# Connector_GTX.net
KiCad netlist of a schematic drawn in Altium Designer
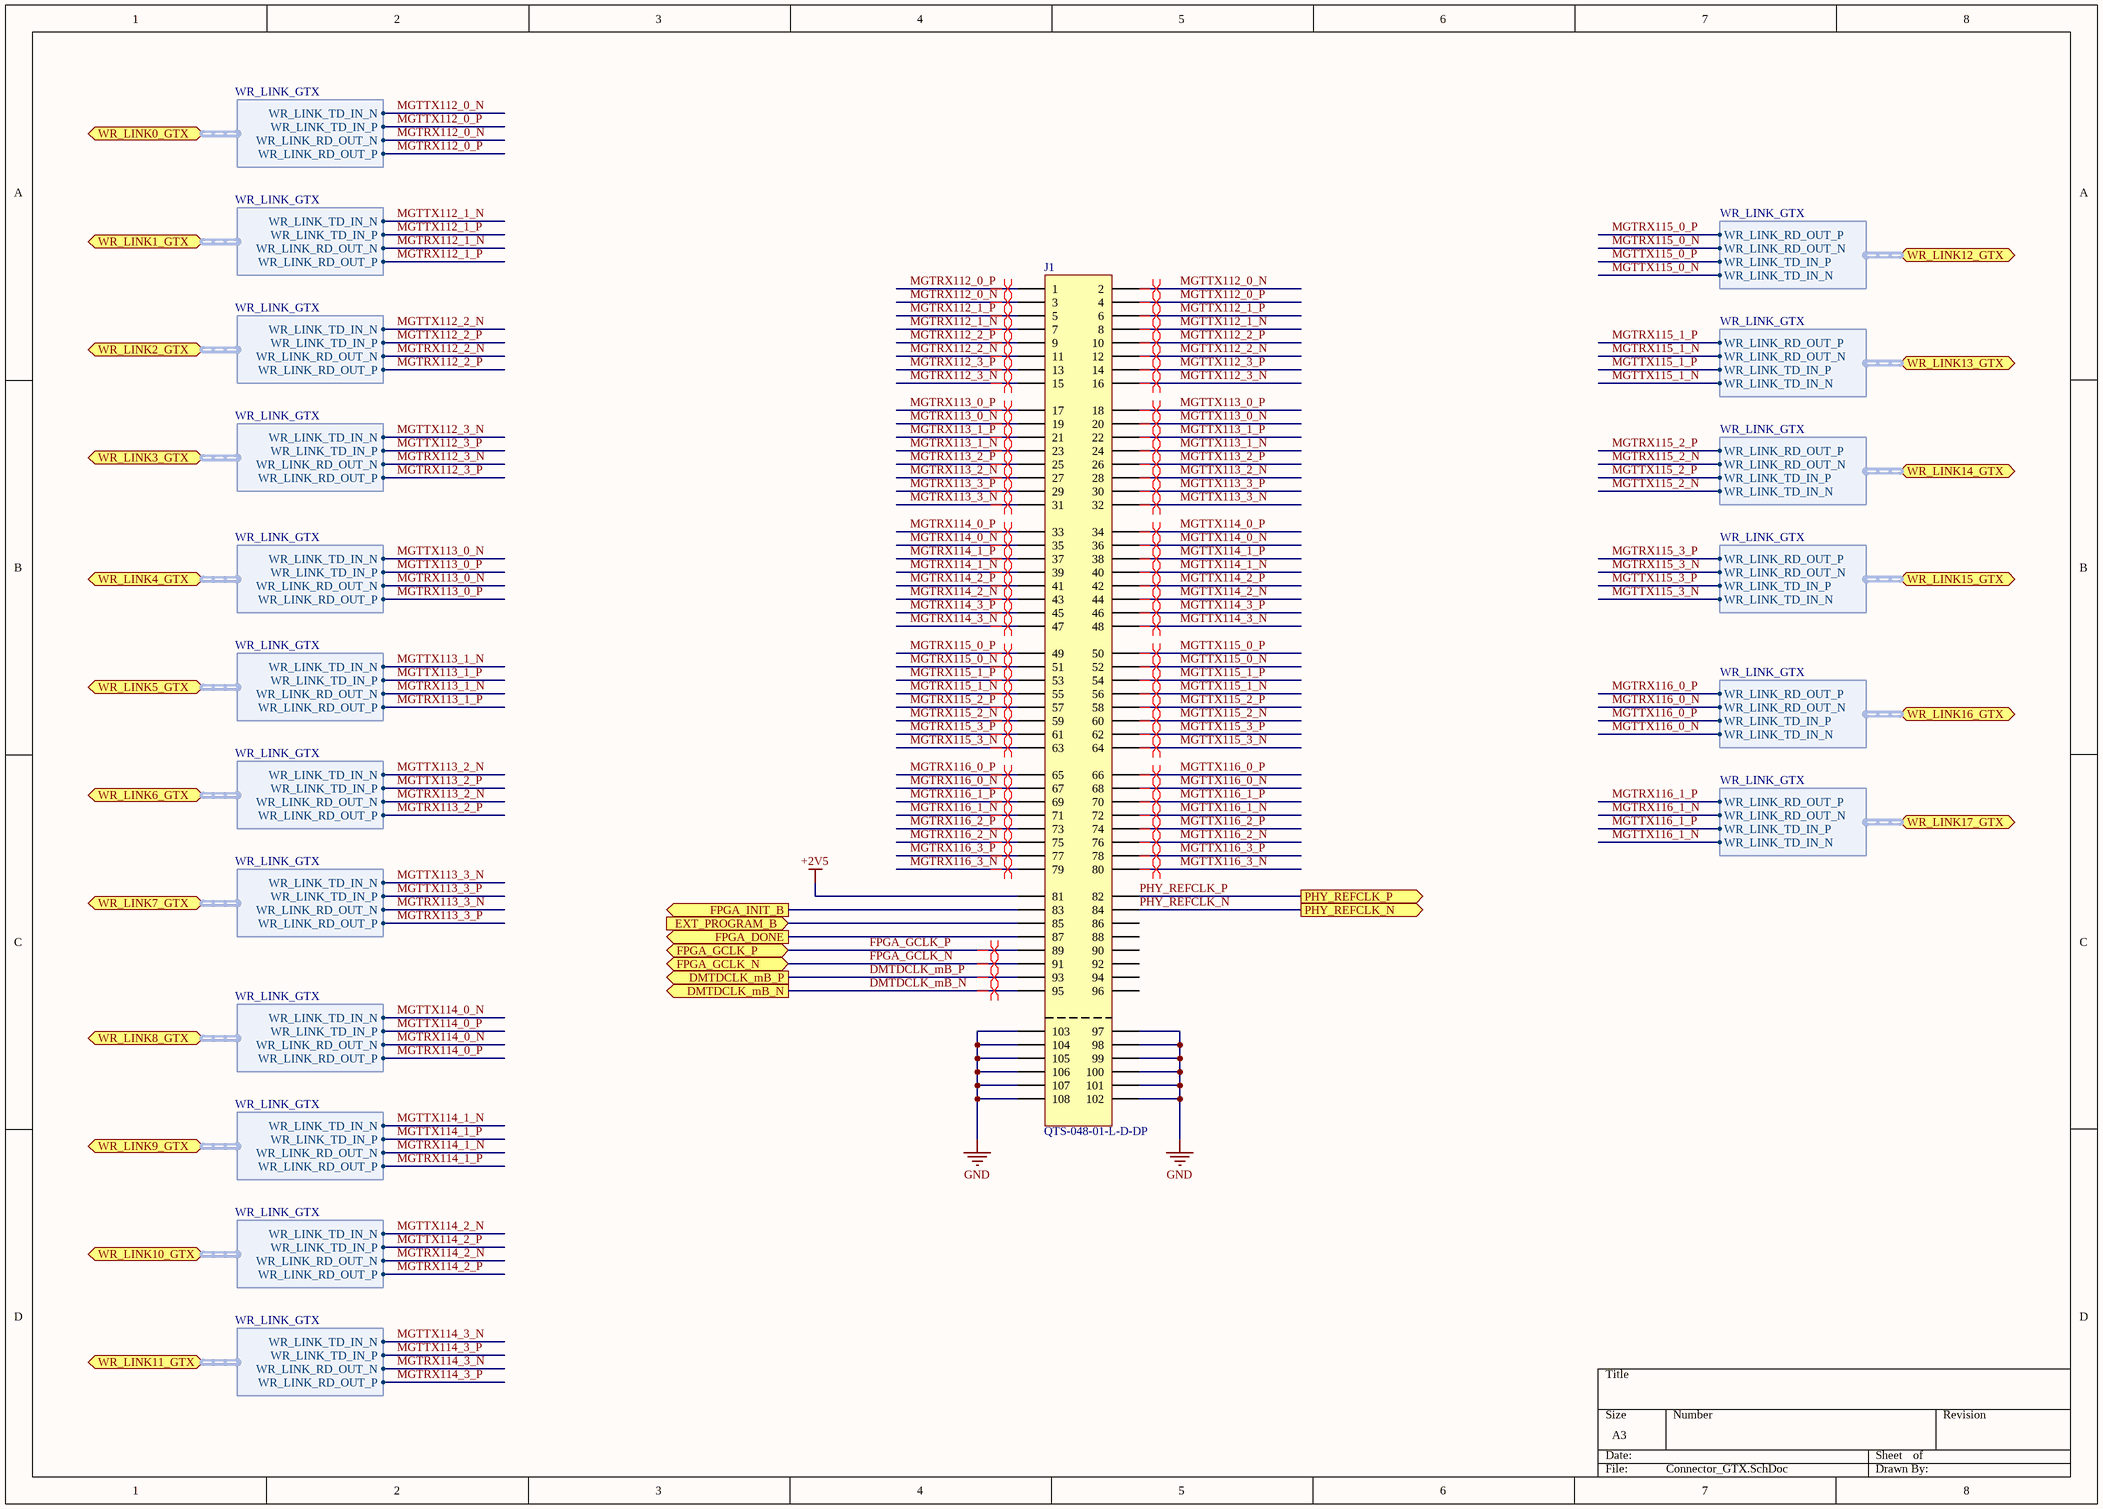
[diagram p0: Connector_GTX.SchDoc]

(export (version "E")
  (design (tool "Eeschema 10.0.6"))
  (components
    (comp (ref "J1")
      (value "QTS-048-01-L-D-DP")
      (footprint "QTS-048-XX-X-D-DP-A")
      (description "High Speed Ground Plane Header")
      (libsource (lib "wr_switch") (part "QTS-048-01-L-D-DP"))
    )
  )
  (nets
    (net (code "2") (name "+2V5") (class "Default")
      (node (ref "J1") (pin "81") (pinfunction "81_81") (pintype "passive"))
    )
    (net (code "3") (name "/DMTDCLK_mB_N") (class "Default")
      (node (ref "J1") (pin "95") (pinfunction "95_95") (pintype "passive"))
    )
    (net (code "4") (name "/DMTDCLK_mB_P") (class "Default")
      (node (ref "J1") (pin "93") (pinfunction "93_93") (pintype "passive"))
    )
    (net (code "5") (name "/EXT_PROGRAM_B") (class "Default")
      (node (ref "J1") (pin "85") (pinfunction "85_85") (pintype "passive"))
    )
    (net (code "6") (name "/FPGA_DONE") (class "Default")
      (node (ref "J1") (pin "87") (pinfunction "87_87") (pintype "passive"))
    )
    (net (code "7") (name "/FPGA_GCLK_N") (class "Default")
      (node (ref "J1") (pin "91") (pinfunction "91_91") (pintype "passive"))
    )
    (net (code "8") (name "/FPGA_GCLK_P") (class "Default")
      (node (ref "J1") (pin "89") (pinfunction "89_89") (pintype "passive"))
    )
    (net (code "9") (name "/FPGA_INIT_B") (class "Default")
      (node (ref "J1") (pin "83") (pinfunction "83_83") (pintype "passive"))
    )
    (net (code "10") (name "/MGTRX112_0_N") (class "Default")
      (node (ref "J1") (pin "3") (pinfunction "3_3") (pintype "passive"))
    )
    (net (code "11") (name "/MGTRX112_0_P") (class "Default")
      (node (ref "J1") (pin "1") (pinfunction "1_1") (pintype "passive"))
    )
    (net (code "12") (name "/MGTRX112_1_N") (class "Default")
      (node (ref "J1") (pin "7") (pinfunction "7_7") (pintype "passive"))
    )
    (net (code "13") (name "/MGTRX112_1_P") (class "Default")
      (node (ref "J1") (pin "5") (pinfunction "5_5") (pintype "passive"))
    )
    (net (code "14") (name "/MGTRX112_2_N") (class "Default")
      (node (ref "J1") (pin "11") (pinfunction "11_11") (pintype "passive"))
    )
    (net (code "15") (name "/MGTRX112_2_P") (class "Default")
      (node (ref "J1") (pin "9") (pinfunction "9_9") (pintype "passive"))
    )
    (net (code "16") (name "/MGTRX112_3_N") (class "Default")
      (node (ref "J1") (pin "15") (pinfunction "15_15") (pintype "passive"))
    )
    (net (code "17") (name "/MGTRX112_3_P") (class "Default")
      (node (ref "J1") (pin "13") (pinfunction "13_13") (pintype "passive"))
    )
    (net (code "18") (name "/MGTRX113_0_N") (class "Default")
      (node (ref "J1") (pin "19") (pinfunction "19_19") (pintype "passive"))
    )
    (net (code "19") (name "/MGTRX113_0_P") (class "Default")
      (node (ref "J1") (pin "17") (pinfunction "17_17") (pintype "passive"))
    )
    (net (code "20") (name "/MGTRX113_1_N") (class "Default")
      (node (ref "J1") (pin "23") (pinfunction "23_23") (pintype "passive"))
    )
    (net (code "21") (name "/MGTRX113_1_P") (class "Default")
      (node (ref "J1") (pin "21") (pinfunction "21_21") (pintype "passive"))
    )
    (net (code "22") (name "/MGTRX113_2_N") (class "Default")
      (node (ref "J1") (pin "27") (pinfunction "27_27") (pintype "passive"))
    )
    (net (code "23") (name "/MGTRX113_2_P") (class "Default")
      (node (ref "J1") (pin "25") (pinfunction "25_25") (pintype "passive"))
    )
    (net (code "24") (name "/MGTRX113_3_N") (class "Default")
      (node (ref "J1") (pin "31") (pinfunction "31_31") (pintype "passive"))
    )
    (net (code "25") (name "/MGTRX113_3_P") (class "Default")
      (node (ref "J1") (pin "29") (pinfunction "29_29") (pintype "passive"))
    )
    (net (code "26") (name "/MGTRX114_0_N") (class "Default")
      (node (ref "J1") (pin "35") (pinfunction "35_35") (pintype "passive"))
    )
    (net (code "27") (name "/MGTRX114_0_P") (class "Default")
      (node (ref "J1") (pin "33") (pinfunction "33_33") (pintype "passive"))
    )
    (net (code "28") (name "/MGTRX114_1_N") (class "Default")
      (node (ref "J1") (pin "39") (pinfunction "39_39") (pintype "passive"))
    )
    (net (code "29") (name "/MGTRX114_1_P") (class "Default")
      (node (ref "J1") (pin "37") (pinfunction "37_37") (pintype "passive"))
    )
    (net (code "30") (name "/MGTRX114_2_N") (class "Default")
      (node (ref "J1") (pin "43") (pinfunction "43_43") (pintype "passive"))
    )
    (net (code "31") (name "/MGTRX114_2_P") (class "Default")
      (node (ref "J1") (pin "41") (pinfunction "41_41") (pintype "passive"))
    )
    (net (code "32") (name "/MGTRX114_3_N") (class "Default")
      (node (ref "J1") (pin "47") (pinfunction "47_47") (pintype "passive"))
    )
    (net (code "33") (name "/MGTRX114_3_P") (class "Default")
      (node (ref "J1") (pin "45") (pinfunction "45_45") (pintype "passive"))
    )
    (net (code "34") (name "/MGTRX115_0_N") (class "Default")
      (node (ref "J1") (pin "51") (pinfunction "51_51") (pintype "passive"))
    )
    (net (code "35") (name "/MGTRX115_0_P") (class "Default")
      (node (ref "J1") (pin "49") (pinfunction "49_49") (pintype "passive"))
    )
    (net (code "36") (name "/MGTRX115_1_N") (class "Default")
      (node (ref "J1") (pin "55") (pinfunction "55_55") (pintype "passive"))
    )
    (net (code "37") (name "/MGTRX115_1_P") (class "Default")
      (node (ref "J1") (pin "53") (pinfunction "53_53") (pintype "passive"))
    )
    (net (code "38") (name "/MGTRX115_2_N") (class "Default")
      (node (ref "J1") (pin "59") (pinfunction "59_59") (pintype "passive"))
    )
    (net (code "39") (name "/MGTRX115_2_P") (class "Default")
      (node (ref "J1") (pin "57") (pinfunction "57_57") (pintype "passive"))
    )
    (net (code "40") (name "/MGTRX115_3_N") (class "Default")
      (node (ref "J1") (pin "63") (pinfunction "63_63") (pintype "passive"))
    )
    (net (code "41") (name "/MGTRX115_3_P") (class "Default")
      (node (ref "J1") (pin "61") (pinfunction "61_61") (pintype "passive"))
    )
    (net (code "42") (name "/MGTRX116_0_N") (class "Default")
      (node (ref "J1") (pin "67") (pinfunction "67_67") (pintype "passive"))
    )
    (net (code "43") (name "/MGTRX116_0_P") (class "Default")
      (node (ref "J1") (pin "65") (pinfunction "65_65") (pintype "passive"))
    )
    (net (code "44") (name "/MGTRX116_1_N") (class "Default")
      (node (ref "J1") (pin "71") (pinfunction "71_71") (pintype "passive"))
    )
    (net (code "45") (name "/MGTRX116_1_P") (class "Default")
      (node (ref "J1") (pin "69") (pinfunction "69_69") (pintype "passive"))
    )
    (net (code "46") (name "/MGTRX116_2_N") (class "Default")
      (node (ref "J1") (pin "75") (pinfunction "75_75") (pintype "passive"))
    )
    (net (code "47") (name "/MGTRX116_2_P") (class "Default")
      (node (ref "J1") (pin "73") (pinfunction "73_73") (pintype "passive"))
    )
    (net (code "48") (name "/MGTRX116_3_N") (class "Default")
      (node (ref "J1") (pin "79") (pinfunction "79_79") (pintype "passive"))
    )
    (net (code "49") (name "/MGTRX116_3_P") (class "Default")
      (node (ref "J1") (pin "77") (pinfunction "77_77") (pintype "passive"))
    )
    (net (code "50") (name "/MGTTX112_0_N") (class "Default")
      (node (ref "J1") (pin "2") (pinfunction "2_2") (pintype "passive"))
    )
    (net (code "51") (name "/MGTTX112_0_P") (class "Default")
      (node (ref "J1") (pin "4") (pinfunction "4_4") (pintype "passive"))
    )
    (net (code "52") (name "/MGTTX112_1_N") (class "Default")
      (node (ref "J1") (pin "8") (pinfunction "8_8") (pintype "passive"))
    )
    (net (code "53") (name "/MGTTX112_1_P") (class "Default")
      (node (ref "J1") (pin "6") (pinfunction "6_6") (pintype "passive"))
    )
    (net (code "54") (name "/MGTTX112_2_N") (class "Default")
      (node (ref "J1") (pin "12") (pinfunction "12_12") (pintype "passive"))
    )
    (net (code "55") (name "/MGTTX112_2_P") (class "Default")
      (node (ref "J1") (pin "10") (pinfunction "10_10") (pintype "passive"))
    )
    (net (code "56") (name "/MGTTX112_3_N") (class "Default")
      (node (ref "J1") (pin "16") (pinfunction "16_16") (pintype "passive"))
    )
    (net (code "57") (name "/MGTTX112_3_P") (class "Default")
      (node (ref "J1") (pin "14") (pinfunction "14_14") (pintype "passive"))
    )
    (net (code "58") (name "/MGTTX113_0_N") (class "Default")
      (node (ref "J1") (pin "20") (pinfunction "20_20") (pintype "passive"))
    )
    (net (code "59") (name "/MGTTX113_0_P") (class "Default")
      (node (ref "J1") (pin "18") (pinfunction "18_18") (pintype "passive"))
    )
    (net (code "60") (name "/MGTTX113_1_N") (class "Default")
      (node (ref "J1") (pin "24") (pinfunction "24_24") (pintype "passive"))
    )
    (net (code "61") (name "/MGTTX113_1_P") (class "Default")
      (node (ref "J1") (pin "22") (pinfunction "22_22") (pintype "passive"))
    )
    (net (code "62") (name "/MGTTX113_2_N") (class "Default")
      (node (ref "J1") (pin "28") (pinfunction "28_28") (pintype "passive"))
    )
    (net (code "63") (name "/MGTTX113_2_P") (class "Default")
      (node (ref "J1") (pin "26") (pinfunction "26_26") (pintype "passive"))
    )
    (net (code "64") (name "/MGTTX113_3_N") (class "Default")
      (node (ref "J1") (pin "32") (pinfunction "32_32") (pintype "passive"))
    )
    (net (code "65") (name "/MGTTX113_3_P") (class "Default")
      (node (ref "J1") (pin "30") (pinfunction "30_30") (pintype "passive"))
    )
    (net (code "66") (name "/MGTTX114_0_N") (class "Default")
      (node (ref "J1") (pin "36") (pinfunction "36_36") (pintype "passive"))
    )
    (net (code "67") (name "/MGTTX114_0_P") (class "Default")
      (node (ref "J1") (pin "34") (pinfunction "34_34") (pintype "passive"))
    )
    (net (code "68") (name "/MGTTX114_1_N") (class "Default")
      (node (ref "J1") (pin "40") (pinfunction "40_40") (pintype "passive"))
    )
    (net (code "69") (name "/MGTTX114_1_P") (class "Default")
      (node (ref "J1") (pin "38") (pinfunction "38_38") (pintype "passive"))
    )
    (net (code "70") (name "/MGTTX114_2_N") (class "Default")
      (node (ref "J1") (pin "44") (pinfunction "44_44") (pintype "passive"))
    )
    (net (code "71") (name "/MGTTX114_2_P") (class "Default")
      (node (ref "J1") (pin "42") (pinfunction "42_42") (pintype "passive"))
    )
    (net (code "72") (name "/MGTTX114_3_N") (class "Default")
      (node (ref "J1") (pin "48") (pinfunction "48_48") (pintype "passive"))
    )
    (net (code "73") (name "/MGTTX114_3_P") (class "Default")
      (node (ref "J1") (pin "46") (pinfunction "46_46") (pintype "passive"))
    )
    (net (code "74") (name "/MGTTX115_0_N") (class "Default")
      (node (ref "J1") (pin "52") (pinfunction "52_52") (pintype "passive"))
    )
    (net (code "75") (name "/MGTTX115_0_P") (class "Default")
      (node (ref "J1") (pin "50") (pinfunction "50_50") (pintype "passive"))
    )
    (net (code "76") (name "/MGTTX115_1_N") (class "Default")
      (node (ref "J1") (pin "56") (pinfunction "56_56") (pintype "passive"))
    )
    (net (code "77") (name "/MGTTX115_1_P") (class "Default")
      (node (ref "J1") (pin "54") (pinfunction "54_54") (pintype "passive"))
    )
    (net (code "78") (name "/MGTTX115_2_N") (class "Default")
      (node (ref "J1") (pin "60") (pinfunction "60_60") (pintype "passive"))
    )
    (net (code "79") (name "/MGTTX115_2_P") (class "Default")
      (node (ref "J1") (pin "58") (pinfunction "58_58") (pintype "passive"))
    )
    (net (code "80") (name "/MGTTX115_3_N") (class "Default")
      (node (ref "J1") (pin "64") (pinfunction "64_64") (pintype "passive"))
    )
    (net (code "81") (name "/MGTTX115_3_P") (class "Default")
      (node (ref "J1") (pin "62") (pinfunction "62_62") (pintype "passive"))
    )
    (net (code "82") (name "/MGTTX116_0_N") (class "Default")
      (node (ref "J1") (pin "68") (pinfunction "68_68") (pintype "passive"))
    )
    (net (code "83") (name "/MGTTX116_0_P") (class "Default")
      (node (ref "J1") (pin "66") (pinfunction "66_66") (pintype "passive"))
    )
    (net (code "84") (name "/MGTTX116_1_N") (class "Default")
      (node (ref "J1") (pin "72") (pinfunction "72_72") (pintype "passive"))
    )
    (net (code "85") (name "/MGTTX116_1_P") (class "Default")
      (node (ref "J1") (pin "70") (pinfunction "70_70") (pintype "passive"))
    )
    (net (code "86") (name "/MGTTX116_2_N") (class "Default")
      (node (ref "J1") (pin "76") (pinfunction "76_76") (pintype "passive"))
    )
    (net (code "87") (name "/MGTTX116_2_P") (class "Default")
      (node (ref "J1") (pin "74") (pinfunction "74_74") (pintype "passive"))
    )
    (net (code "88") (name "/MGTTX116_3_N") (class "Default")
      (node (ref "J1") (pin "80") (pinfunction "80_80") (pintype "passive"))
    )
    (net (code "89") (name "/MGTTX116_3_P") (class "Default")
      (node (ref "J1") (pin "78") (pinfunction "78_78") (pintype "passive"))
    )
    (net (code "90") (name "/PHY_REFCLK_N") (class "Default")
      (node (ref "J1") (pin "84") (pinfunction "84_84") (pintype "passive"))
    )
    (net (code "91") (name "/PHY_REFCLK_P") (class "Default")
      (node (ref "J1") (pin "82") (pinfunction "82_82") (pintype "passive"))
    )
    (net (code "93") (name "GND") (class "Default")
      (node (ref "J1") (pin "100") (pinfunction "100_100") (pintype "passive"))
      (node (ref "J1") (pin "101") (pinfunction "101_101") (pintype "passive"))
      (node (ref "J1") (pin "102") (pinfunction "102_102") (pintype "passive"))
      (node (ref "J1") (pin "103") (pinfunction "103_103") (pintype "passive"))
      (node (ref "J1") (pin "104") (pinfunction "104_104") (pintype "passive"))
      (node (ref "J1") (pin "105") (pinfunction "105_105") (pintype "passive"))
      (node (ref "J1") (pin "106") (pinfunction "106_106") (pintype "passive"))
      (node (ref "J1") (pin "107") (pinfunction "107_107") (pintype "passive"))
      (node (ref "J1") (pin "108") (pinfunction "108_108") (pintype "passive"))
      (node (ref "J1") (pin "97") (pinfunction "97_97") (pintype "passive"))
      (node (ref "J1") (pin "98") (pinfunction "98_98") (pintype "passive"))
      (node (ref "J1") (pin "99") (pinfunction "99_99") (pintype "passive"))
    )
    (net (code "94") (name "unconnected-(J1-Pad86)") (class "Default")
      (node (ref "J1") (pin "86") (pinfunction "86_86") (pintype "passive"))
    )
    (net (code "95") (name "unconnected-(J1-Pad88)") (class "Default")
      (node (ref "J1") (pin "88") (pinfunction "88_88") (pintype "passive"))
    )
    (net (code "96") (name "unconnected-(J1-Pad90)") (class "Default")
      (node (ref "J1") (pin "90") (pinfunction "90_90") (pintype "passive"))
    )
    (net (code "97") (name "unconnected-(J1-Pad92)") (class "Default")
      (node (ref "J1") (pin "92") (pinfunction "92_92") (pintype "passive"))
    )
    (net (code "98") (name "unconnected-(J1-Pad94)") (class "Default")
      (node (ref "J1") (pin "94") (pinfunction "94_94") (pintype "passive"))
    )
    (net (code "99") (name "unconnected-(J1-Pad96)") (class "Default")
      (node (ref "J1") (pin "96") (pinfunction "96_96") (pintype "passive"))
    )
  )
)
